# BaiguangESI.net
KiCad netlist of a schematic drawn in Altium Designer
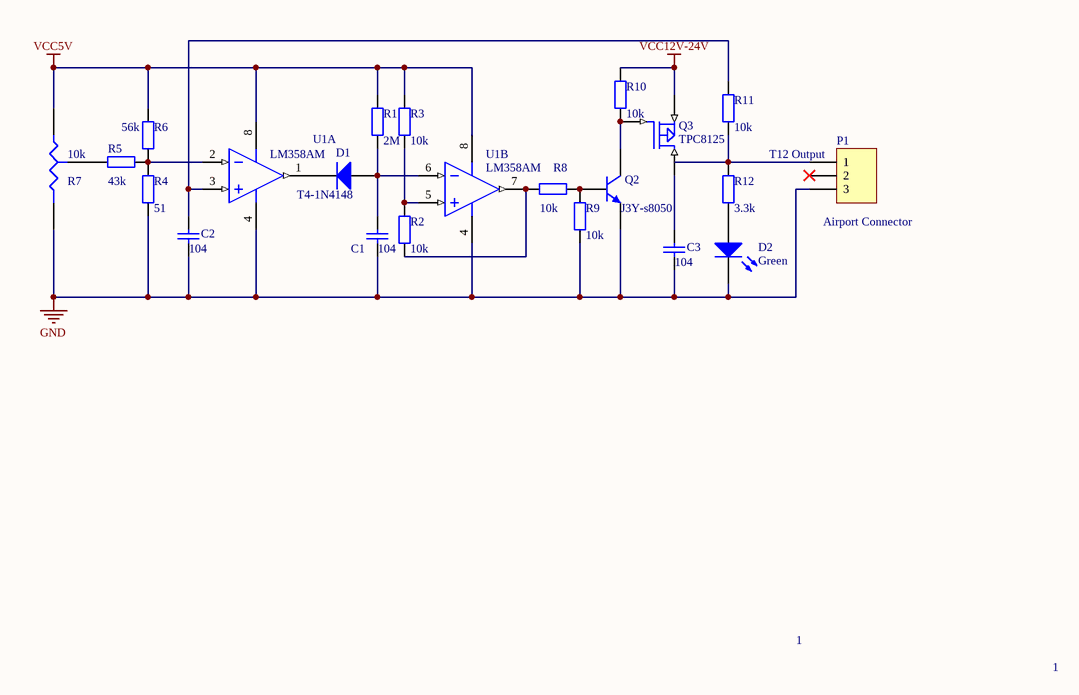
[diagram p0: BaiguangESI.SchDoc]

(export (version "E")
  (design (tool "Eeschema 10.0.6"))
  (components
    (comp (ref "C1")
      (value "104")
      (footprint "RAD-0.3")
      (description "Capacitor")
      (fields (field (name "PUBLISHER") "Altium Limited"))
      (libsource (lib "Miscellaneous Devices") (part "Cap"))
    )
    (comp (ref "C2")
      (value "104")
      (footprint "RAD-0.3")
      (description "Capacitor")
      (fields (field (name "PUBLISHER") "Altium Limited"))
      (libsource (lib "Miscellaneous Devices") (part "Cap"))
    )
    (comp (ref "C3")
      (value "104")
      (footprint "RAD-0.3")
      (description "Capacitor")
      (fields (field (name "PUBLISHER") "Altium Limited"))
      (libsource (lib "Miscellaneous Devices") (part "Cap"))
    )
    (comp (ref "D1")
      (value "T4-1N4148")
      (footprint "SMC")
      (description "Default Diode")
      (fields (field (name "PUBLISHER") "Altium Limited"))
      (libsource (lib "Miscellaneous Devices") (part "Diode"))
    )
    (comp (ref "D2")
      (value "Green")
      (footprint "LED-0")
      (description "Typical INFRARED GaAs LED")
      (fields (field (name "PUBLISHER") "Altium Limited"))
      (libsource (lib "Miscellaneous Devices") (part "LED0"))
    )
    (comp (ref "P1")
      (value "Airport Connector")
      (footprint "HDR1X3")
      (description "Header, 3-Pin")
      (fields (field (name "PUBLISHER") "Altium Limited"))
      (libsource (lib "Miscellaneous Connectors") (part "Header 3"))
    )
    (comp (ref "Q2")
      (value "J3Y-s8050")
      (footprint "TO-92A")
      (description "NPN General Purpose Amplifier")
      (fields (field (name "PUBLISHER") "Altium Limited"))
      (libsource (lib "Miscellaneous Devices") (part "2N3904"))
    )
    (comp (ref "Q3") (value "TPC8125") (libsource (lib "场效应管及可控硅") (part "MOSFET P")))
    (comp (ref "R1")
      (value "2M")
      (footprint "AXIAL-0.4")
      (description "Resistor")
      (fields (field (name "PUBLISHER") "Altium Limited"))
      (libsource (lib "") (part "Res2_1"))
    )
    (comp (ref "R2")
      (value "10k")
      (footprint "AXIAL-0.4")
      (description "Resistor")
      (fields (field (name "PUBLISHER") "Altium Limited"))
      (libsource (lib "") (part "Res2_1"))
    )
    (comp (ref "R3")
      (value "10k")
      (footprint "AXIAL-0.4")
      (description "Resistor")
      (fields (field (name "PUBLISHER") "Altium Limited"))
      (libsource (lib "") (part "Res2_1"))
    )
    (comp (ref "R4")
      (value "51")
      (footprint "AXIAL-0.4")
      (description "Resistor")
      (fields (field (name "PUBLISHER") "Altium Limited"))
      (libsource (lib "") (part "Res2_1"))
    )
    (comp (ref "R5")
      (value "43k")
      (footprint "AXIAL-0.4")
      (description "Resistor")
      (fields (field (name "PUBLISHER") "Altium Limited"))
      (libsource (lib "") (part "Res2_2"))
    )
    (comp (ref "R6")
      (value "56k")
      (footprint "AXIAL-0.4")
      (description "Resistor")
      (fields (field (name "PUBLISHER") "Altium Limited"))
      (libsource (lib "") (part "Res2_1"))
    )
    (comp (ref "R7")
      (value "10k")
      (footprint "VR3")
      (description "Tapped Resistor")
      (fields (field (name "PUBLISHER") "Altium Limited"))
      (libsource (lib "Miscellaneous Devices") (part "Res Tap"))
    )
    (comp (ref "R8")
      (value "10k")
      (footprint "AXIAL-0.4")
      (description "Resistor")
      (fields (field (name "PUBLISHER") "Altium Limited"))
      (libsource (lib "") (part "Res2_2"))
    )
    (comp (ref "R9")
      (value "10k")
      (footprint "AXIAL-0.4")
      (description "Resistor")
      (fields (field (name "PUBLISHER") "Altium Limited"))
      (libsource (lib "Miscellaneous Devices") (part "Res2"))
    )
    (comp (ref "R10")
      (value "10k")
      (footprint "AXIAL-0.4")
      (description "Resistor")
      (fields (field (name "PUBLISHER") "Altium Limited"))
      (libsource (lib "Miscellaneous Devices") (part "Res2"))
    )
    (comp (ref "R11")
      (value "10k")
      (footprint "AXIAL-0.4")
      (description "Resistor")
      (fields (field (name "PUBLISHER") "Altium Limited"))
      (libsource (lib "") (part "Res2_1"))
    )
    (comp (ref "R12")
      (value "3.3k")
      (footprint "AXIAL-0.4")
      (description "Resistor")
      (fields (field (name "PUBLISHER") "Altium Limited"))
      (libsource (lib "Miscellaneous Devices") (part "Res2"))
    )
    (comp (ref "U1")
      (value "LM358AM")
      (footprint "M08A_N")
      (description "Low Power Dual Operational Amplifier, 8-pin Narrow SOIC")
      (fields
        (field (name "MANUFACTURER") "National Semiconductor")
        (field (name "PUBLISHER") "Altium Limited")
      )
      (libsource (lib "NSC Amplifier") (part "LM358AM"))
    )
  )
  (nets
    (net (code "1") (name "GND") (class "Default")
      (node (ref "C1") (pin "1") (pinfunction "1_1") (pintype "passive"))
      (node (ref "C2") (pin "1") (pinfunction "1_1") (pintype "passive"))
      (node (ref "C3") (pin "1") (pinfunction "1_1") (pintype "passive"))
      (node (ref "D2") (pin "2") (pinfunction "K_2") (pintype "passive"))
      (node (ref "P1") (pin "3") (pinfunction "3_3") (pintype "passive"))
      (node (ref "Q2") (pin "1") (pinfunction "E_1") (pintype "passive"))
      (node (ref "R4") (pin "1") (pinfunction "1_1") (pintype "passive"))
      (node (ref "R7") (pin "2") (pinfunction "B_2") (pintype "passive"))
      (node (ref "R9") (pin "2") (pinfunction "2_2") (pintype "passive"))
      (node (ref "U1") (pin "4") (pinfunction "GND_4") (pintype "power_in"))
    )
    (net (code "2") (name "Net-(D1-A)") (class "Default")
      (node (ref "C1") (pin "2") (pinfunction "2_2") (pintype "passive"))
      (node (ref "D1") (pin "1") (pinfunction "A_1") (pintype "passive"))
      (node (ref "R1") (pin "1") (pinfunction "1_1") (pintype "passive"))
      (node (ref "U1") (pin "6") (pinfunction "INB-_6") (pintype "input"))
    )
    (net (code "3") (name "Net-(D1-K)") (class "Default")
      (node (ref "D1") (pin "2") (pinfunction "K_2") (pintype "passive"))
      (node (ref "U1") (pin "1") (pinfunction "OUTA_1") (pintype "output"))
    )
    (net (code "4") (name "Net-(D2-A)") (class "Default")
      (node (ref "D2") (pin "1") (pinfunction "A_1") (pintype "passive"))
      (node (ref "R12") (pin "2") (pinfunction "2_2") (pintype "passive"))
    )
    (net (code "5") (name "Net-(P1-Pad1)") (class "Default")
      (node (ref "P1") (pin "1") (pinfunction "1_1") (pintype "passive"))
      (node (ref "R11") (pin "1") (pinfunction "1_1") (pintype "passive"))
      (node (ref "R12") (pin "1") (pinfunction "1_1") (pintype "passive"))
    )
    (net (code "6") (name "Net-(Q2-B)") (class "Default")
      (node (ref "Q2") (pin "2") (pinfunction "B_2") (pintype "passive"))
      (node (ref "R8") (pin "1") (pinfunction "1_1") (pintype "passive"))
      (node (ref "R9") (pin "1") (pinfunction "1_1") (pintype "passive"))
    )
    (net (code "7") (name "Net-(Q2-C)") (class "Default")
      (node (ref "Q2") (pin "3") (pinfunction "C_3") (pintype "passive"))
      (node (ref "Q3") (pin "1") (pinfunction "G_1") (pintype "input"))
      (node (ref "R10") (pin "2") (pinfunction "2_2") (pintype "passive"))
    )
    (net (code "8") (name "Net-(Q3-D)") (class "Default")
      (node (ref "C3") (pin "2") (pinfunction "2_2") (pintype "passive"))
      (node (ref "Q3") (pin "2") (pinfunction "D_2") (pintype "input"))
    )
    (net (code "9") (name "Net-(R7-TAP)") (class "Default")
      (node (ref "R5") (pin "2") (pinfunction "2_2") (pintype "passive"))
      (node (ref "R7") (pin "3") (pinfunction "TAP_3") (pintype "passive"))
    )
    (net (code "10") (name "Net-(U1A-INA+)") (class "Default")
      (node (ref "C2") (pin "2") (pinfunction "2_2") (pintype "passive"))
      (node (ref "R11") (pin "2") (pinfunction "2_2") (pintype "passive"))
      (node (ref "U1") (pin "3") (pinfunction "INA+_3") (pintype "input"))
    )
    (net (code "11") (name "Net-(U1A-INA-)") (class "Default")
      (node (ref "R4") (pin "2") (pinfunction "2_2") (pintype "passive"))
      (node (ref "R5") (pin "1") (pinfunction "1_1") (pintype "passive"))
      (node (ref "R6") (pin "1") (pinfunction "1_1") (pintype "passive"))
      (node (ref "U1") (pin "2") (pinfunction "INA-_2") (pintype "input"))
    )
    (net (code "12") (name "Net-(U1B-INB+)") (class "Default")
      (node (ref "R2") (pin "2") (pinfunction "2_2") (pintype "passive"))
      (node (ref "R3") (pin "1") (pinfunction "1_1") (pintype "passive"))
      (node (ref "U1") (pin "5") (pinfunction "INB+_5") (pintype "input"))
    )
    (net (code "13") (name "Net-(U1B-OUTB)") (class "Default")
      (node (ref "R2") (pin "1") (pinfunction "1_1") (pintype "passive"))
      (node (ref "R8") (pin "2") (pinfunction "2_2") (pintype "passive"))
      (node (ref "U1") (pin "7") (pinfunction "OUTB_7") (pintype "output"))
    )
    (net (code "14") (name "VCC5V") (class "Default")
      (node (ref "R1") (pin "2") (pinfunction "2_2") (pintype "passive"))
      (node (ref "R3") (pin "2") (pinfunction "2_2") (pintype "passive"))
      (node (ref "R6") (pin "2") (pinfunction "2_2") (pintype "passive"))
      (node (ref "R7") (pin "1") (pinfunction "A_1") (pintype "passive"))
      (node (ref "U1") (pin "8") (pinfunction "V+_8") (pintype "power_in"))
    )
    (net (code "15") (name "VCC12V-24V") (class "Default")
      (node (ref "Q3") (pin "3") (pinfunction "S_3") (pintype "input"))
      (node (ref "R10") (pin "1") (pinfunction "1_1") (pintype "passive"))
    )
    (net (code "16") (name "unconnected-(P1-Pad2)") (class "Default")
      (node (ref "P1") (pin "2") (pinfunction "2_2") (pintype "passive+no_connect"))
    )
  )
)
